# Falhaber_DC_CONN.net
KiCad netlist of a schematic drawn in EAGLE
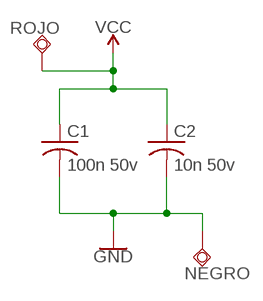
[diagram p0: schematic, sheet 1]

(export (version "E")
  (design (tool "Eeschema 10.0.6"))
  (components
    (comp (ref "C1")
      (value "100n 50v")
      (footprint "eagle-import:C0805")
      (libsource (lib "eagle-import") (part "C-USC0805"))
    )
    (comp (ref "C2")
      (value "10n 50v")
      (footprint "eagle-import:C0805")
      (libsource (lib "eagle-import") (part "C-USC0805"))
    )
    (comp (ref "NEGRO")
      (value "TESTPAD_TPSQTP10SQ")
      (footprint "eagle-import:TESTPAD_TP10SQ")
      (libsource (lib "eagle-import") (part "TESTPAD_TPSQTP10SQ"))
    )
    (comp (ref "ROJO")
      (value "TESTPAD_TPSQTP10SQ")
      (footprint "eagle-import:TESTPAD_TP10SQ")
      (libsource (lib "eagle-import") (part "TESTPAD_TPSQTP10SQ"))
    )
  )
  (nets
    (net (code "1") (name "GND") (class "Default")
      (node (ref "C1") (pin "2") (pinfunction "2_2") (pintype "passive"))
      (node (ref "C2") (pin "2") (pinfunction "2_2") (pintype "passive"))
      (node (ref "NEGRO") (pin "TP") (pinfunction "TP_TP") (pintype "input"))
    )
    (net (code "2") (name "VCC") (class "Default")
      (node (ref "C1") (pin "1") (pinfunction "1_1") (pintype "passive"))
      (node (ref "C2") (pin "1") (pinfunction "1_1") (pintype "passive"))
      (node (ref "ROJO") (pin "TP") (pinfunction "TP_TP") (pintype "input"))
    )
  )
)
